# Power_Distribution_-_Camera.net
KiCad netlist of a schematic drawn in Altium Designer
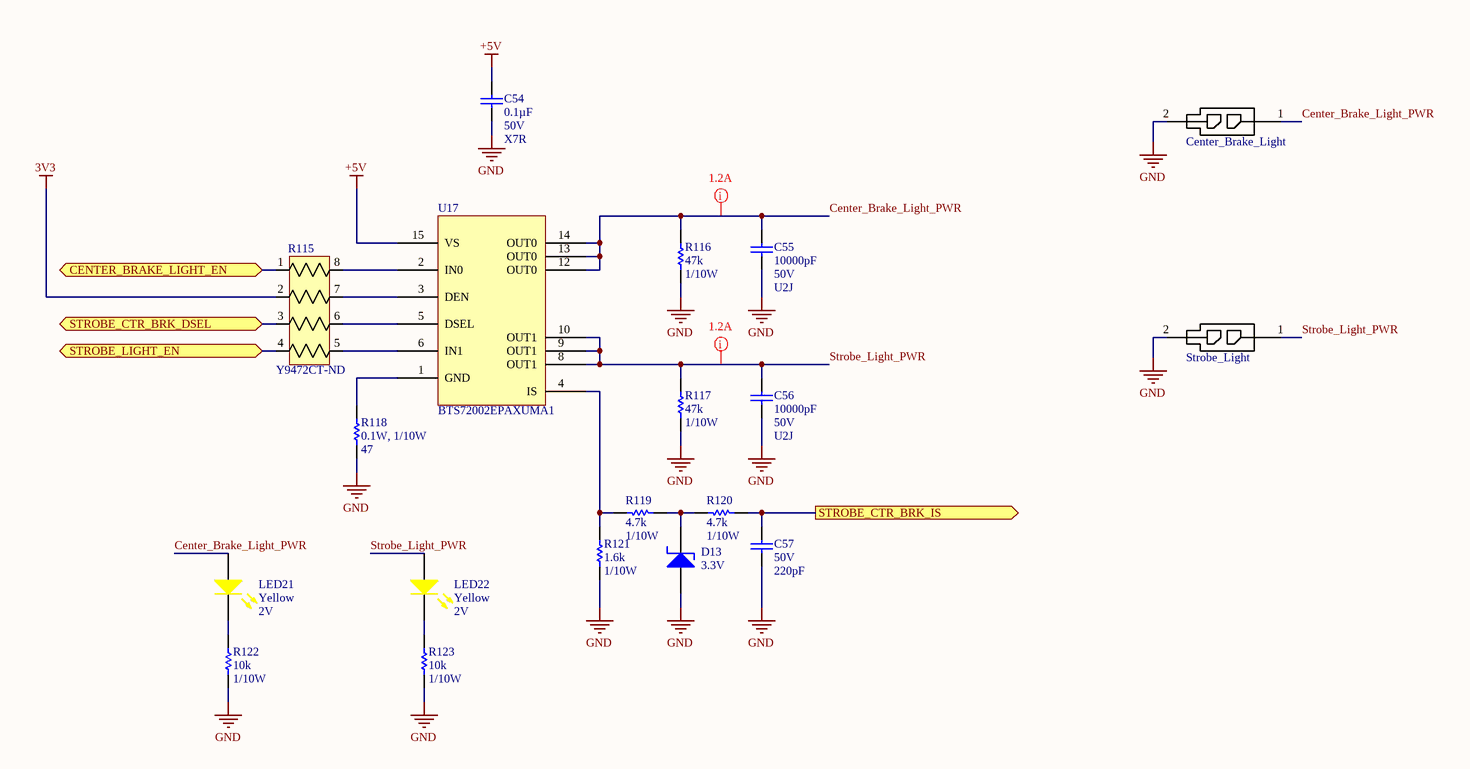
[diagram p0: Power Distribution - Camera.SchDoc]

(export (version "E")
  (design (tool "Eeschema 10.0.6"))
  (components
    (comp (ref "C54")
      (value "CAP CER 0.1UF 50V 10% X7R 0603")
      (footprint "CAP, 0603")
      (description "0.10µF ±10% 50V Ceramic Capacitor X7R 0603 (1608 Metric)")
      (fields
        (field (name "TOLERANCE") "±10%")
        (field (name "CAPACITANCE") "0.1µF")
        (field (name "VOLTAGE") "50V")
        (field (name "TEMPERATURE COEFFICIENT") "X7R")
      )
      (libsource (lib "Schematic Diagrams") (part "CAP CER 0.1UF 50V 10% X7R 0603"))
    )
    (comp (ref "C55")
      (value "CAP CER 10nF 50V 5% X7R 0603")
      (footprint "CAP, 0603")
      (description "10000pF ±5% 50V Ceramic Capacitor U2J 0603 (1608 Metric)")
      (fields
        (field (name "TOLERANCE") "±5%")
        (field (name "CAPACITANCE") "10000pF")
        (field (name "VOLTAGE") "50V")
        (field (name "TEMPERATURE COEFFICIENT") "U2J")
      )
      (libsource (lib "Schematic Diagrams") (part "CAP CER 10nF 50V 5% X7R 0603"))
    )
    (comp (ref "C56")
      (value "CAP CER 10nF 50V 5% X7R 0603")
      (footprint "CAP, 0603")
      (description "10000pF ±5% 50V Ceramic Capacitor U2J 0603 (1608 Metric)")
      (fields
        (field (name "TOLERANCE") "±5%")
        (field (name "CAPACITANCE") "10000pF")
        (field (name "VOLTAGE") "50V")
        (field (name "TEMPERATURE COEFFICIENT") "U2J")
      )
      (libsource (lib "Schematic Diagrams") (part "CAP CER 10nF 50V 5% X7R 0603"))
    )
    (comp (ref "C57")
      (value "CAP CER 220PF 50V C0G/NP0 0603")
      (footprint "CAP, 0603")
      (description "220pF ±5% 50V Ceramic Capacitor C0G, NP0 0603 (1608 Metric)")
      (fields
        (field (name "MANUFACTURER") "KEMET")
        (field (name "TOLERANCE") "5%")
        (field (name "VOLTAGE RATING") "50V")
        (field (name "CAPACITANCE") "220pF")
      )
      (libsource (lib "Schematic Diagrams") (part "CAP CER 220PF 50V C0G/NP0 0603"))
    )
    (comp (ref "Center_Brake_Light")
      (value "CONN 2POS MICRO-FIT 3mm")
      (footprint "CONN, 2POS MICRO-FIT")
      (description "Connector Header Through Hole 2 position")
      (fields (field (name "MANUFACTURER") "Molex") (field (name "MANUFACTURER PART NUMBER") "43045-0227"))
      (libsource (lib "Schematic Diagrams") (part "CONN 2POS MICRO-FIT 3mm"))
    )
    (comp (ref "D13")
      (value "DIODE ZENER 3.3V 200MW SOD323")
      (footprint "sod-323")
      (description "Zener Diode 3.3V 200mW ±5% Surface Mount SOD-323")
      (fields (field (name "VOLTAGE") "3.3V"))
      (libsource (lib "Schematic Diagrams") (part "DIODE ZENER 3.3V 200MW SOD323"))
    )
    (comp (ref "LED21")
      (value "LED YELLOW CLEAR 2.1V 0603")
      (footprint "LED_0603")
      (description "Yellow 590nm LED Indication - Discrete 2V 0603 (1608 Metric)")
      (fields
        (field (name "MANUFACTURER") "Wurth Electronics Inc.")
        (field (name "MANUFACTURER PART NUMBER") "150060YS75000")
        (field (name "COLOR") "Yellow")
        (field (name "VOLTAGE - FORWARD (VF) (TYP)") "2V")
      )
      (libsource (lib "Schematic Diagrams") (part "LED YELLOW CLEAR 2.1V 0603"))
    )
    (comp (ref "LED22")
      (value "LED YELLOW CLEAR 2.1V 0603")
      (footprint "LED_0603")
      (description "Yellow 590nm LED Indication - Discrete 2V 0603 (1608 Metric)")
      (fields
        (field (name "MANUFACTURER") "Wurth Electronics Inc.")
        (field (name "MANUFACTURER PART NUMBER") "150060YS75000")
        (field (name "COLOR") "Yellow")
        (field (name "VOLTAGE - FORWARD (VF) (TYP)") "2V")
      )
      (libsource (lib "Schematic Diagrams") (part "LED YELLOW CLEAR 2.1V 0603"))
    )
    (comp (ref "R115")
      (value "RES ARRAY 4 RES 4.7K OHM 1206")
      (footprint "RES ARRAY 4RES 1206")
      (fields (field (name "TOLERANCE") "±5%") (field (name "SUPPLIER PART NUMBER 1") "Y9472CT-ND"))
      (libsource (lib "Schematic Diagrams") (part "RES ARRAY 4 RES 4.7K OHM 1206"))
    )
    (comp (ref "R116")
      (value "RES 47K OHM 1% 1/10W 0603")
      (footprint "RES, 0603")
      (description "47 kOhms ±1% 0.1W, 1/10W Chip Resistor 0603 (1608 Metric) Automotive AEC-Q200 Thick Film")
      (fields
        (field (name "MANUFACTURER") "Panasonic")
        (field (name "MANUFACTURER PART NUMBER") "ERJ3EKF4702V")
        (field (name "RESISTANCE") "47k")
        (field (name "POWER RATING") "1/10W")
      )
      (libsource (lib "Schematic Diagrams") (part "RES 47K OHM 1% 1/10W 0603"))
    )
    (comp (ref "R117")
      (value "RES 47K OHM 1% 1/10W 0603")
      (footprint "RES, 0603")
      (description "47 kOhms ±1% 0.1W, 1/10W Chip Resistor 0603 (1608 Metric) Automotive AEC-Q200 Thick Film")
      (fields
        (field (name "MANUFACTURER") "Panasonic")
        (field (name "MANUFACTURER PART NUMBER") "ERJ3EKF4702V")
        (field (name "RESISTANCE") "47k")
        (field (name "POWER RATING") "1/10W")
      )
      (libsource (lib "Schematic Diagrams") (part "RES 47K OHM 1% 1/10W 0603"))
    )
    (comp (ref "R118")
      (value "RES SMD 47 OHM 1% 1/10W 0603")
      (footprint "RES, 0603")
      (fields
        (field (name "TOLERANCE") "±1%")
        (field (name "POWER (WATTS)") "0.1W, 1/10W")
        (field (name "VALUES") "47")
      )
      (libsource (lib "Schematic Diagrams") (part "RES SMD 47 OHM 1% 1/10W 0603"))
    )
    (comp (ref "R119")
      (value "RES 4.7K OHM 1% 1/10W 0603")
      (footprint "RES, 0603")
      (description "4.7k Ohm ±1% 0.1W, 1/10W Chip Resistor 0603 (1608 Metric) Moisture Resistant Thick Film")
      (fields
        (field (name "TOLERANCE") "±1%")
        (field (name "RESISTANCE (OHMS)") "4.7k")
        (field (name "POWER (WATTS)") "1/10W")
      )
      (libsource (lib "Schematic Diagrams") (part "RES 4.7K OHM 1% 1/10W 0603"))
    )
    (comp (ref "R120")
      (value "RES 4.7K OHM 1% 1/10W 0603")
      (footprint "RES, 0603")
      (description "4.7k Ohm ±1% 0.1W, 1/10W Chip Resistor 0603 (1608 Metric) Moisture Resistant Thick Film")
      (fields
        (field (name "TOLERANCE") "±1%")
        (field (name "RESISTANCE (OHMS)") "4.7k")
        (field (name "POWER (WATTS)") "1/10W")
      )
      (libsource (lib "Schematic Diagrams") (part "RES 4.7K OHM 1% 1/10W 0603"))
    )
    (comp (ref "R121")
      (value "RES 1.6K OHM 1% 1/10W 0603")
      (footprint "RES, 0603")
      (description "1.6 kOhms ±1% 0.1W, 1/10W Chip Resistor 0603 (1608 Metric) Moisture Resistant Thick Film")
      (fields
        (field (name "MANUFACTURER") "Yageo")
        (field (name "MANUFACTURER PART NUMBER") "RC0603FR-071K6L")
        (field (name "RESISTANCE") "1.6k")
        (field (name "POWER RATING") "1/10W")
      )
      (libsource (lib "Schematic Diagrams") (part "RES 1.6K OHM 1% 1/10W 0603"))
    )
    (comp (ref "R122")
      (value "RES 10K OHM 1% 1/10W 0603")
      (footprint "RES, 0603")
      (description "RES SMD 10K OHM 1% 1/10W 0603")
      (fields
        (field (name "TOLERANCE") "±1%")
        (field (name "RESISTANCE") "10k")
        (field (name "POWER") "1/10W")
      )
      (libsource (lib "Schematic Diagrams") (part "RES 10K OHM 1% 1/10W 0603"))
    )
    (comp (ref "R123")
      (value "RES 10K OHM 1% 1/10W 0603")
      (footprint "RES, 0603")
      (description "RES SMD 10K OHM 1% 1/10W 0603")
      (fields
        (field (name "TOLERANCE") "±1%")
        (field (name "RESISTANCE") "10k")
        (field (name "POWER") "1/10W")
      )
      (libsource (lib "Schematic Diagrams") (part "RES 10K OHM 1% 1/10W 0603"))
    )
    (comp (ref "Strobe_Light")
      (value "CONN 2POS MICRO-FIT 3mm")
      (footprint "CONN, 2POS MICRO-FIT")
      (description "Connector Header Through Hole 2 position")
      (fields (field (name "MANUFACTURER") "Molex") (field (name "MANUFACTURER PART NUMBER") "43045-0227"))
      (libsource (lib "Schematic Diagrams") (part "CONN 2POS MICRO-FIT 3mm"))
    )
    (comp (ref "U17")
      (value "IC LOAD SWITCH BTS7200-2EPA PG-TSDSO-14_1")
      (footprint "IC LOAD SWITCH PG-TSDSO-14-22")
      (description "Power Switch/Driver 1:1 N-Channel 1.2A PG-TSDSO-14-22")
      (fields
        (field (name "MANUFACTURER") "Infineon")
        (field (name "MANUFACTURER PART NUMBER") "BTS72002EPAXUMA1")
      )
      (libsource (lib "Schematic Diagrams") (part "IC LOAD SWITCH BTS7200-2EPA PG-TSDSO-14_1"))
    )
  )
  (nets
    (net (code "1") (name "+5V") (class "Default")
      (node (ref "C54") (pin "1") (pinfunction "1_1") (pintype "passive"))
      (node (ref "U17") (pin "15") (pinfunction "VS_15") (pintype "passive"))
    )
    (net (code "2") (name "/CENTER_BRAKE_LIGHT_EN") (class "Default")
      (node (ref "R115") (pin "1") (pinfunction "1_1") (pintype "passive"))
    )
    (net (code "3") (name "/Center_Brake_Light_PWR") (class "Default")
      (node (ref "C55") (pin "1") (pinfunction "1_1") (pintype "passive"))
      (node (ref "Center_Brake_Light") (pin "1") (pinfunction "1_1") (pintype "passive"))
      (node (ref "LED21") (pin "1") (pinfunction "A_1") (pintype "passive"))
      (node (ref "R116") (pin "1") (pinfunction "1_1") (pintype "passive"))
      (node (ref "U17") (pin "12") (pinfunction "OUT0_12") (pintype "passive"))
      (node (ref "U17") (pin "13") (pinfunction "OUT0_13") (pintype "passive"))
      (node (ref "U17") (pin "14") (pinfunction "OUT0_14") (pintype "passive"))
    )
    (net (code "4") (name "/STROBE_CTR_BRK_DSEL") (class "Default")
      (node (ref "R115") (pin "3") (pinfunction "3_3") (pintype "passive"))
    )
    (net (code "5") (name "/STROBE_CTR_BRK_IS") (class "Default")
      (node (ref "C57") (pin "1") (pinfunction "1_1") (pintype "passive"))
      (node (ref "R120") (pin "1") (pinfunction "1_1") (pintype "passive"))
    )
    (net (code "6") (name "/STROBE_LIGHT_EN") (class "Default")
      (node (ref "R115") (pin "4") (pinfunction "4_4") (pintype "passive"))
    )
    (net (code "7") (name "/Strobe_Light_PWR") (class "Default")
      (node (ref "C56") (pin "1") (pinfunction "1_1") (pintype "passive"))
      (node (ref "LED22") (pin "1") (pinfunction "A_1") (pintype "passive"))
      (node (ref "R117") (pin "1") (pinfunction "1_1") (pintype "passive"))
      (node (ref "Strobe_Light") (pin "1") (pinfunction "1_1") (pintype "passive"))
      (node (ref "U17") (pin "10") (pinfunction "OUT1_10") (pintype "passive"))
      (node (ref "U17") (pin "8") (pinfunction "OUT1_8") (pintype "passive"))
      (node (ref "U17") (pin "9") (pinfunction "OUT1_9") (pintype "passive"))
    )
    (net (code "8") (name "3V3") (class "Default")
      (node (ref "R115") (pin "2") (pinfunction "2_2") (pintype "passive"))
    )
    (net (code "9") (name "GND") (class "Default")
      (node (ref "C54") (pin "2") (pinfunction "2_2") (pintype "passive"))
      (node (ref "C55") (pin "2") (pinfunction "2_2") (pintype "passive"))
      (node (ref "C56") (pin "2") (pinfunction "2_2") (pintype "passive"))
      (node (ref "C57") (pin "2") (pinfunction "2_2") (pintype "passive"))
      (node (ref "Center_Brake_Light") (pin "2") (pinfunction "2_2") (pintype "passive"))
      (node (ref "D13") (pin "1") (pinfunction "A_1") (pintype "passive"))
      (node (ref "R116") (pin "2") (pinfunction "2_2") (pintype "passive"))
      (node (ref "R117") (pin "2") (pinfunction "2_2") (pintype "passive"))
      (node (ref "R118") (pin "2") (pinfunction "2_2") (pintype "passive"))
      (node (ref "R121") (pin "2") (pinfunction "2_2") (pintype "passive"))
      (node (ref "R122") (pin "2") (pinfunction "2_2") (pintype "passive"))
      (node (ref "R123") (pin "2") (pinfunction "2_2") (pintype "passive"))
      (node (ref "Strobe_Light") (pin "2") (pinfunction "2_2") (pintype "passive"))
    )
    (net (code "10") (name "Net-(D13-K)") (class "Default")
      (node (ref "D13") (pin "2") (pinfunction "K_2") (pintype "passive"))
      (node (ref "R119") (pin "1") (pinfunction "1_1") (pintype "passive"))
      (node (ref "R120") (pin "2") (pinfunction "2_2") (pintype "passive"))
    )
    (net (code "11") (name "Net-(LED21-K)") (class "Default")
      (node (ref "LED21") (pin "2") (pinfunction "K_2") (pintype "passive"))
      (node (ref "R122") (pin "1") (pinfunction "1_1") (pintype "passive"))
    )
    (net (code "12") (name "Net-(LED22-K)") (class "Default")
      (node (ref "LED22") (pin "2") (pinfunction "K_2") (pintype "passive"))
      (node (ref "R123") (pin "1") (pinfunction "1_1") (pintype "passive"))
    )
    (net (code "13") (name "Net-(U17-DEN)") (class "Default")
      (node (ref "R115") (pin "7") (pinfunction "7_7") (pintype "passive"))
      (node (ref "U17") (pin "3") (pinfunction "DEN_3") (pintype "passive"))
    )
    (net (code "14") (name "Net-(U17-DSEL)") (class "Default")
      (node (ref "R115") (pin "6") (pinfunction "6_6") (pintype "passive"))
      (node (ref "U17") (pin "5") (pinfunction "DSEL_5") (pintype "passive"))
    )
    (net (code "15") (name "Net-(U17-GND)") (class "Default")
      (node (ref "R118") (pin "1") (pinfunction "1_1") (pintype "passive"))
      (node (ref "U17") (pin "1") (pinfunction "GND_1") (pintype "passive"))
    )
    (net (code "16") (name "Net-(U17-IN0)") (class "Default")
      (node (ref "R115") (pin "8") (pinfunction "8_8") (pintype "passive"))
      (node (ref "U17") (pin "2") (pinfunction "IN0_2") (pintype "passive"))
    )
    (net (code "17") (name "Net-(U17-IN1)") (class "Default")
      (node (ref "R115") (pin "5") (pinfunction "5_5") (pintype "passive"))
      (node (ref "U17") (pin "6") (pinfunction "IN1_6") (pintype "passive"))
    )
    (net (code "18") (name "Net-(U17-IS)") (class "Default")
      (node (ref "R119") (pin "2") (pinfunction "2_2") (pintype "passive"))
      (node (ref "R121") (pin "1") (pinfunction "1_1") (pintype "passive"))
      (node (ref "U17") (pin "4") (pinfunction "IS_4") (pintype "passive"))
    )
  )
)
